# Sistema_anti-allagamento_ELETTRONICA.net
KiCad netlist of a schematic drawn in EAGLE
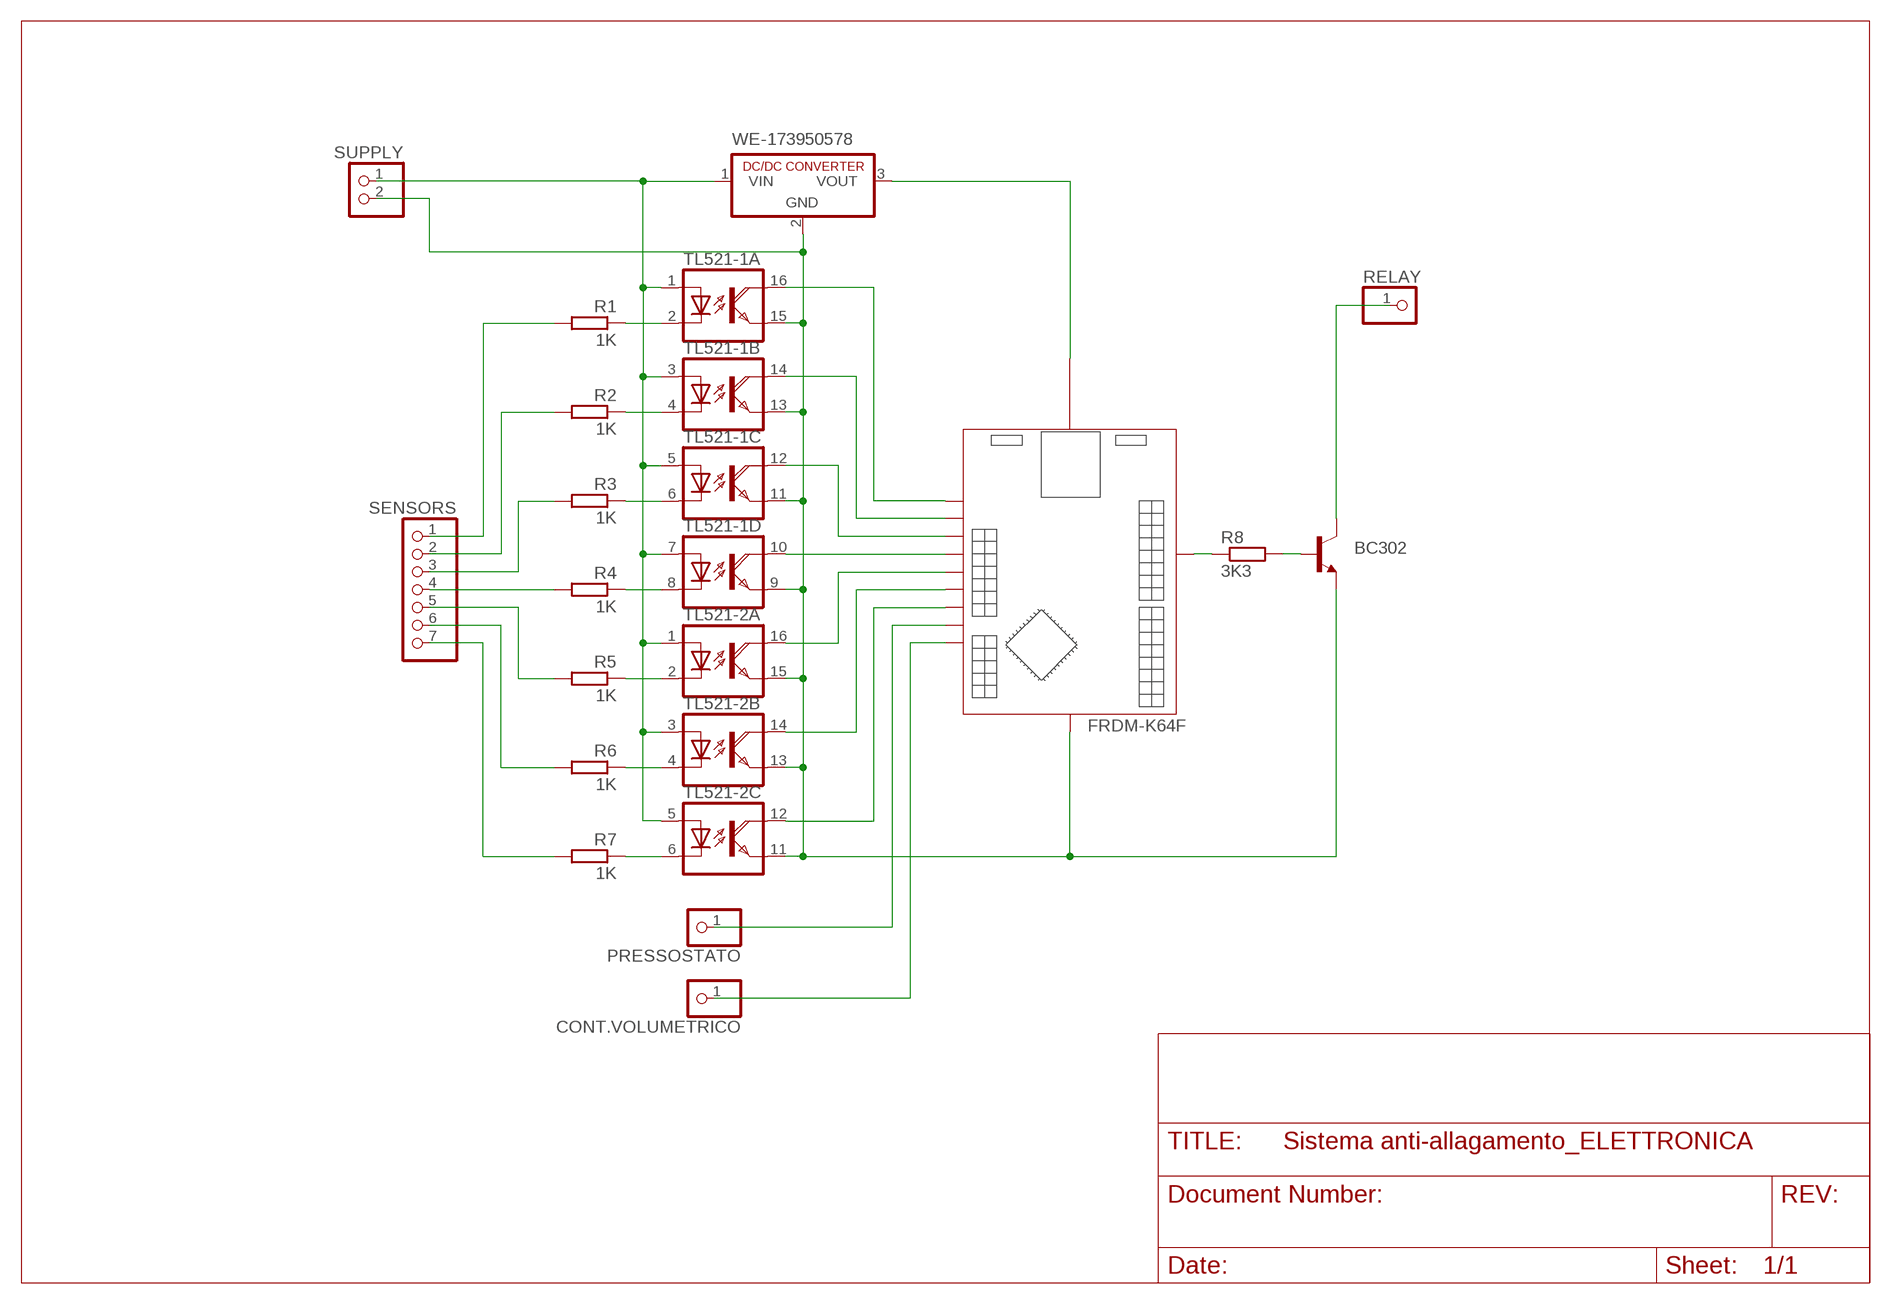
[diagram p0: schematic, sheet 1]

(export (version "E")
  (design (tool "Eeschema 10.0.6"))
  (components
    (comp (ref "BC302")
      (value "BFY50")
      (footprint "eagle-import:TO39")
      (libsource (lib "eagle-import") (part "BFY50"))
    )
    (comp (ref "CONT.VOLUMETRICO")
      (value "PINHD-1X1")
      (footprint "eagle-import:1X01")
      (libsource (lib "eagle-import") (part "PINHD-1X1"))
    )
    (comp (ref "PRESSOSTATO")
      (value "PINHD-1X1")
      (footprint "eagle-import:1X01")
      (libsource (lib "eagle-import") (part "PINHD-1X1"))
    )
    (comp (ref "R1")
      (value "1K")
      (footprint "eagle-import:0207_7")
      (libsource (lib "eagle-import") (part "R-EU_0207/7"))
    )
    (comp (ref "R2")
      (value "1K")
      (footprint "eagle-import:0207_7")
      (libsource (lib "eagle-import") (part "R-EU_0207/7"))
    )
    (comp (ref "R3")
      (value "1K")
      (footprint "eagle-import:0207_7")
      (libsource (lib "eagle-import") (part "R-EU_0207/7"))
    )
    (comp (ref "R4")
      (value "1K")
      (footprint "eagle-import:0207_7")
      (libsource (lib "eagle-import") (part "R-EU_0207/7"))
    )
    (comp (ref "R5")
      (value "1K")
      (footprint "eagle-import:0207_7")
      (libsource (lib "eagle-import") (part "R-EU_0207/7"))
    )
    (comp (ref "R6")
      (value "1K")
      (footprint "eagle-import:0207_7")
      (libsource (lib "eagle-import") (part "R-EU_0207/7"))
    )
    (comp (ref "R7")
      (value "1K")
      (footprint "eagle-import:0207_7")
      (libsource (lib "eagle-import") (part "R-EU_0207/7"))
    )
    (comp (ref "R8")
      (value "3K3")
      (footprint "eagle-import:0204_7")
      (libsource (lib "eagle-import") (part "R-EU_0204/7"))
    )
    (comp (ref "RELAY")
      (value "PINHD-1X1")
      (footprint "eagle-import:1X01")
      (libsource (lib "eagle-import") (part "PINHD-1X1"))
    )
    (comp (ref "SENSORS")
      (value "PINHD-1X7")
      (footprint "eagle-import:1X07")
      (libsource (lib "eagle-import") (part "PINHD-1X7"))
    )
    (comp (ref "SUPPLY")
      (value "PINHD-1X2")
      (footprint "eagle-import:1X02")
      (libsource (lib "eagle-import") (part "PINHD-1X2"))
    )
    (comp (ref "TL521-1")
      (value "TIL199")
      (footprint "eagle-import:DIL16")
      (fields (field (name "MPN") "TIL 199"))
      (libsource (lib "eagle-import") (part "TIL199"))
    )
    (comp (ref "TL521-2")
      (value "TIL199")
      (footprint "eagle-import:DIL16")
      (fields (field (name "MPN") "TIL 199"))
      (libsource (lib "eagle-import") (part "TIL199"))
    )
    (comp (ref "WE-173950578")
      (value "R-78C1.8-1.0")
      (footprint "eagle-import:SIP3")
      (libsource (lib "eagle-import") (part "R-78C-1.01.8"))
    )
  )
  (nets
    (net (code "1") (name "Net-(BC302-B)") (class "Default")
      (node (ref "BC302") (pin "2") (pinfunction "B_2") (pintype "passive"))
      (node (ref "R8") (pin "2") (pinfunction "2_2") (pintype "passive"))
    )
    (net (code "2") (name "Net-(BC302-C)") (class "Default")
      (node (ref "BC302") (pin "3") (pinfunction "C_3") (pintype "passive"))
      (node (ref "RELAY") (pin "1") (pinfunction "1_1") (pintype "passive"))
    )
    (net (code "3") (name "Net-(BC302-E)") (class "Default")
      (node (ref "BC302") (pin "1") (pinfunction "E_1") (pintype "passive"))
      (node (ref "SUPPLY") (pin "2") (pinfunction "2_2") (pintype "passive"))
      (node (ref "TL521-1") (pin "11") (pinfunction "EMI_11") (pintype "passive"))
      (node (ref "TL521-1") (pin "13") (pinfunction "EMI_13") (pintype "passive"))
      (node (ref "TL521-1") (pin "15") (pinfunction "EMI_15") (pintype "passive"))
      (node (ref "TL521-1") (pin "9") (pinfunction "EMI_9") (pintype "passive"))
      (node (ref "TL521-2") (pin "11") (pinfunction "EMI_11") (pintype "passive"))
      (node (ref "TL521-2") (pin "13") (pinfunction "EMI_13") (pintype "passive"))
      (node (ref "TL521-2") (pin "15") (pinfunction "EMI_15") (pintype "passive"))
      (node (ref "WE-173950578") (pin "2") (pinfunction "GND_2") (pintype "passive"))
    )
    (net (code "4") (name "Net-(R1-Pad2)") (class "Default")
      (node (ref "R1") (pin "2") (pinfunction "2_2") (pintype "passive"))
      (node (ref "SENSORS") (pin "1") (pinfunction "1_1") (pintype "passive"))
    )
    (net (code "5") (name "Net-(R2-Pad2)") (class "Default")
      (node (ref "R2") (pin "2") (pinfunction "2_2") (pintype "passive"))
      (node (ref "SENSORS") (pin "2") (pinfunction "2_2") (pintype "passive"))
    )
    (net (code "6") (name "Net-(R3-Pad2)") (class "Default")
      (node (ref "R3") (pin "2") (pinfunction "2_2") (pintype "passive"))
      (node (ref "SENSORS") (pin "3") (pinfunction "3_3") (pintype "passive"))
    )
    (net (code "7") (name "Net-(R4-Pad2)") (class "Default")
      (node (ref "R4") (pin "2") (pinfunction "2_2") (pintype "passive"))
      (node (ref "SENSORS") (pin "4") (pinfunction "4_4") (pintype "passive"))
    )
    (net (code "8") (name "Net-(R5-Pad2)") (class "Default")
      (node (ref "R5") (pin "2") (pinfunction "2_2") (pintype "passive"))
      (node (ref "SENSORS") (pin "5") (pinfunction "5_5") (pintype "passive"))
    )
    (net (code "9") (name "Net-(R6-Pad2)") (class "Default")
      (node (ref "R6") (pin "2") (pinfunction "2_2") (pintype "passive"))
      (node (ref "SENSORS") (pin "6") (pinfunction "6_6") (pintype "passive"))
    )
    (net (code "10") (name "Net-(R7-Pad2)") (class "Default")
      (node (ref "R7") (pin "2") (pinfunction "2_2") (pintype "passive"))
      (node (ref "SENSORS") (pin "7") (pinfunction "7_7") (pintype "passive"))
    )
    (net (code "11") (name "Net-(TL521-1A-A)") (class "Default")
      (node (ref "SUPPLY") (pin "1") (pinfunction "1_1") (pintype "passive"))
      (node (ref "TL521-1") (pin "1") (pinfunction "A_1") (pintype "passive"))
      (node (ref "TL521-1") (pin "3") (pinfunction "A_3") (pintype "passive"))
      (node (ref "TL521-1") (pin "5") (pinfunction "A_5") (pintype "passive"))
      (node (ref "TL521-1") (pin "7") (pinfunction "A_7") (pintype "passive"))
      (node (ref "TL521-2") (pin "1") (pinfunction "A_1") (pintype "passive"))
      (node (ref "TL521-2") (pin "3") (pinfunction "A_3") (pintype "passive"))
      (node (ref "TL521-2") (pin "5") (pinfunction "A_5") (pintype "passive"))
      (node (ref "WE-173950578") (pin "1") (pinfunction "VIN_1") (pintype "passive"))
    )
    (net (code "12") (name "Net-(TL521-1A-C)") (class "Default")
      (node (ref "R1") (pin "1") (pinfunction "1_1") (pintype "passive"))
      (node (ref "TL521-1") (pin "2") (pinfunction "C_2") (pintype "passive"))
    )
    (net (code "13") (name "Net-(TL521-1B-C)") (class "Default")
      (node (ref "R2") (pin "1") (pinfunction "1_1") (pintype "passive"))
      (node (ref "TL521-1") (pin "4") (pinfunction "C_4") (pintype "passive"))
    )
    (net (code "14") (name "Net-(TL521-1C-C)") (class "Default")
      (node (ref "R3") (pin "1") (pinfunction "1_1") (pintype "passive"))
      (node (ref "TL521-1") (pin "6") (pinfunction "C_6") (pintype "passive"))
    )
    (net (code "15") (name "Net-(TL521-1D-C)") (class "Default")
      (node (ref "R4") (pin "1") (pinfunction "1_1") (pintype "passive"))
      (node (ref "TL521-1") (pin "8") (pinfunction "C_8") (pintype "passive"))
    )
    (net (code "16") (name "Net-(TL521-2A-C)") (class "Default")
      (node (ref "R5") (pin "1") (pinfunction "1_1") (pintype "passive"))
      (node (ref "TL521-2") (pin "2") (pinfunction "C_2") (pintype "passive"))
    )
    (net (code "17") (name "Net-(TL521-2B-C)") (class "Default")
      (node (ref "R6") (pin "1") (pinfunction "1_1") (pintype "passive"))
      (node (ref "TL521-2") (pin "4") (pinfunction "C_4") (pintype "passive"))
    )
    (net (code "18") (name "Net-(TL521-2C-C)") (class "Default")
      (node (ref "R7") (pin "1") (pinfunction "1_1") (pintype "passive"))
      (node (ref "TL521-2") (pin "6") (pinfunction "C_6") (pintype "passive"))
    )
    (net (code "19") (name "unconnected-(CONT.VOLUMETRICO-Pad1)") (class "Default")
      (node (ref "CONT.VOLUMETRICO") (pin "1") (pinfunction "1_1") (pintype "passive"))
    )
    (net (code "20") (name "unconnected-(PRESSOSTATO-Pad1)") (class "Default")
      (node (ref "PRESSOSTATO") (pin "1") (pinfunction "1_1") (pintype "passive"))
    )
    (net (code "21") (name "unconnected-(R8-Pad1)") (class "Default")
      (node (ref "R8") (pin "1") (pinfunction "1_1") (pintype "passive"))
    )
    (net (code "22") (name "unconnected-(TL521-1A-COL-Pad16)") (class "Default")
      (node (ref "TL521-1") (pin "16") (pinfunction "COL_16") (pintype "passive"))
    )
    (net (code "23") (name "unconnected-(TL521-1B-COL-Pad14)") (class "Default")
      (node (ref "TL521-1") (pin "14") (pinfunction "COL_14") (pintype "passive"))
    )
    (net (code "24") (name "unconnected-(TL521-1C-COL-Pad12)") (class "Default")
      (node (ref "TL521-1") (pin "12") (pinfunction "COL_12") (pintype "passive"))
    )
    (net (code "25") (name "unconnected-(TL521-1D-COL-Pad10)") (class "Default")
      (node (ref "TL521-1") (pin "10") (pinfunction "COL_10") (pintype "passive"))
    )
    (net (code "26") (name "unconnected-(TL521-2A-COL-Pad16)") (class "Default")
      (node (ref "TL521-2") (pin "16") (pinfunction "COL_16") (pintype "passive"))
    )
    (net (code "27") (name "unconnected-(TL521-2B-COL-Pad14)") (class "Default")
      (node (ref "TL521-2") (pin "14") (pinfunction "COL_14") (pintype "passive"))
    )
    (net (code "28") (name "unconnected-(TL521-2C-COL-Pad12)") (class "Default")
      (node (ref "TL521-2") (pin "12") (pinfunction "COL_12") (pintype "passive"))
    )
    (net (code "29") (name "unconnected-(WE-173950578-VOUT-Pad3)") (class "Default")
      (node (ref "WE-173950578") (pin "3") (pinfunction "VOUT_3") (pintype "passive"))
    )
  )
)
